# Main.net
KiCad netlist of a schematic drawn in Altium Designer
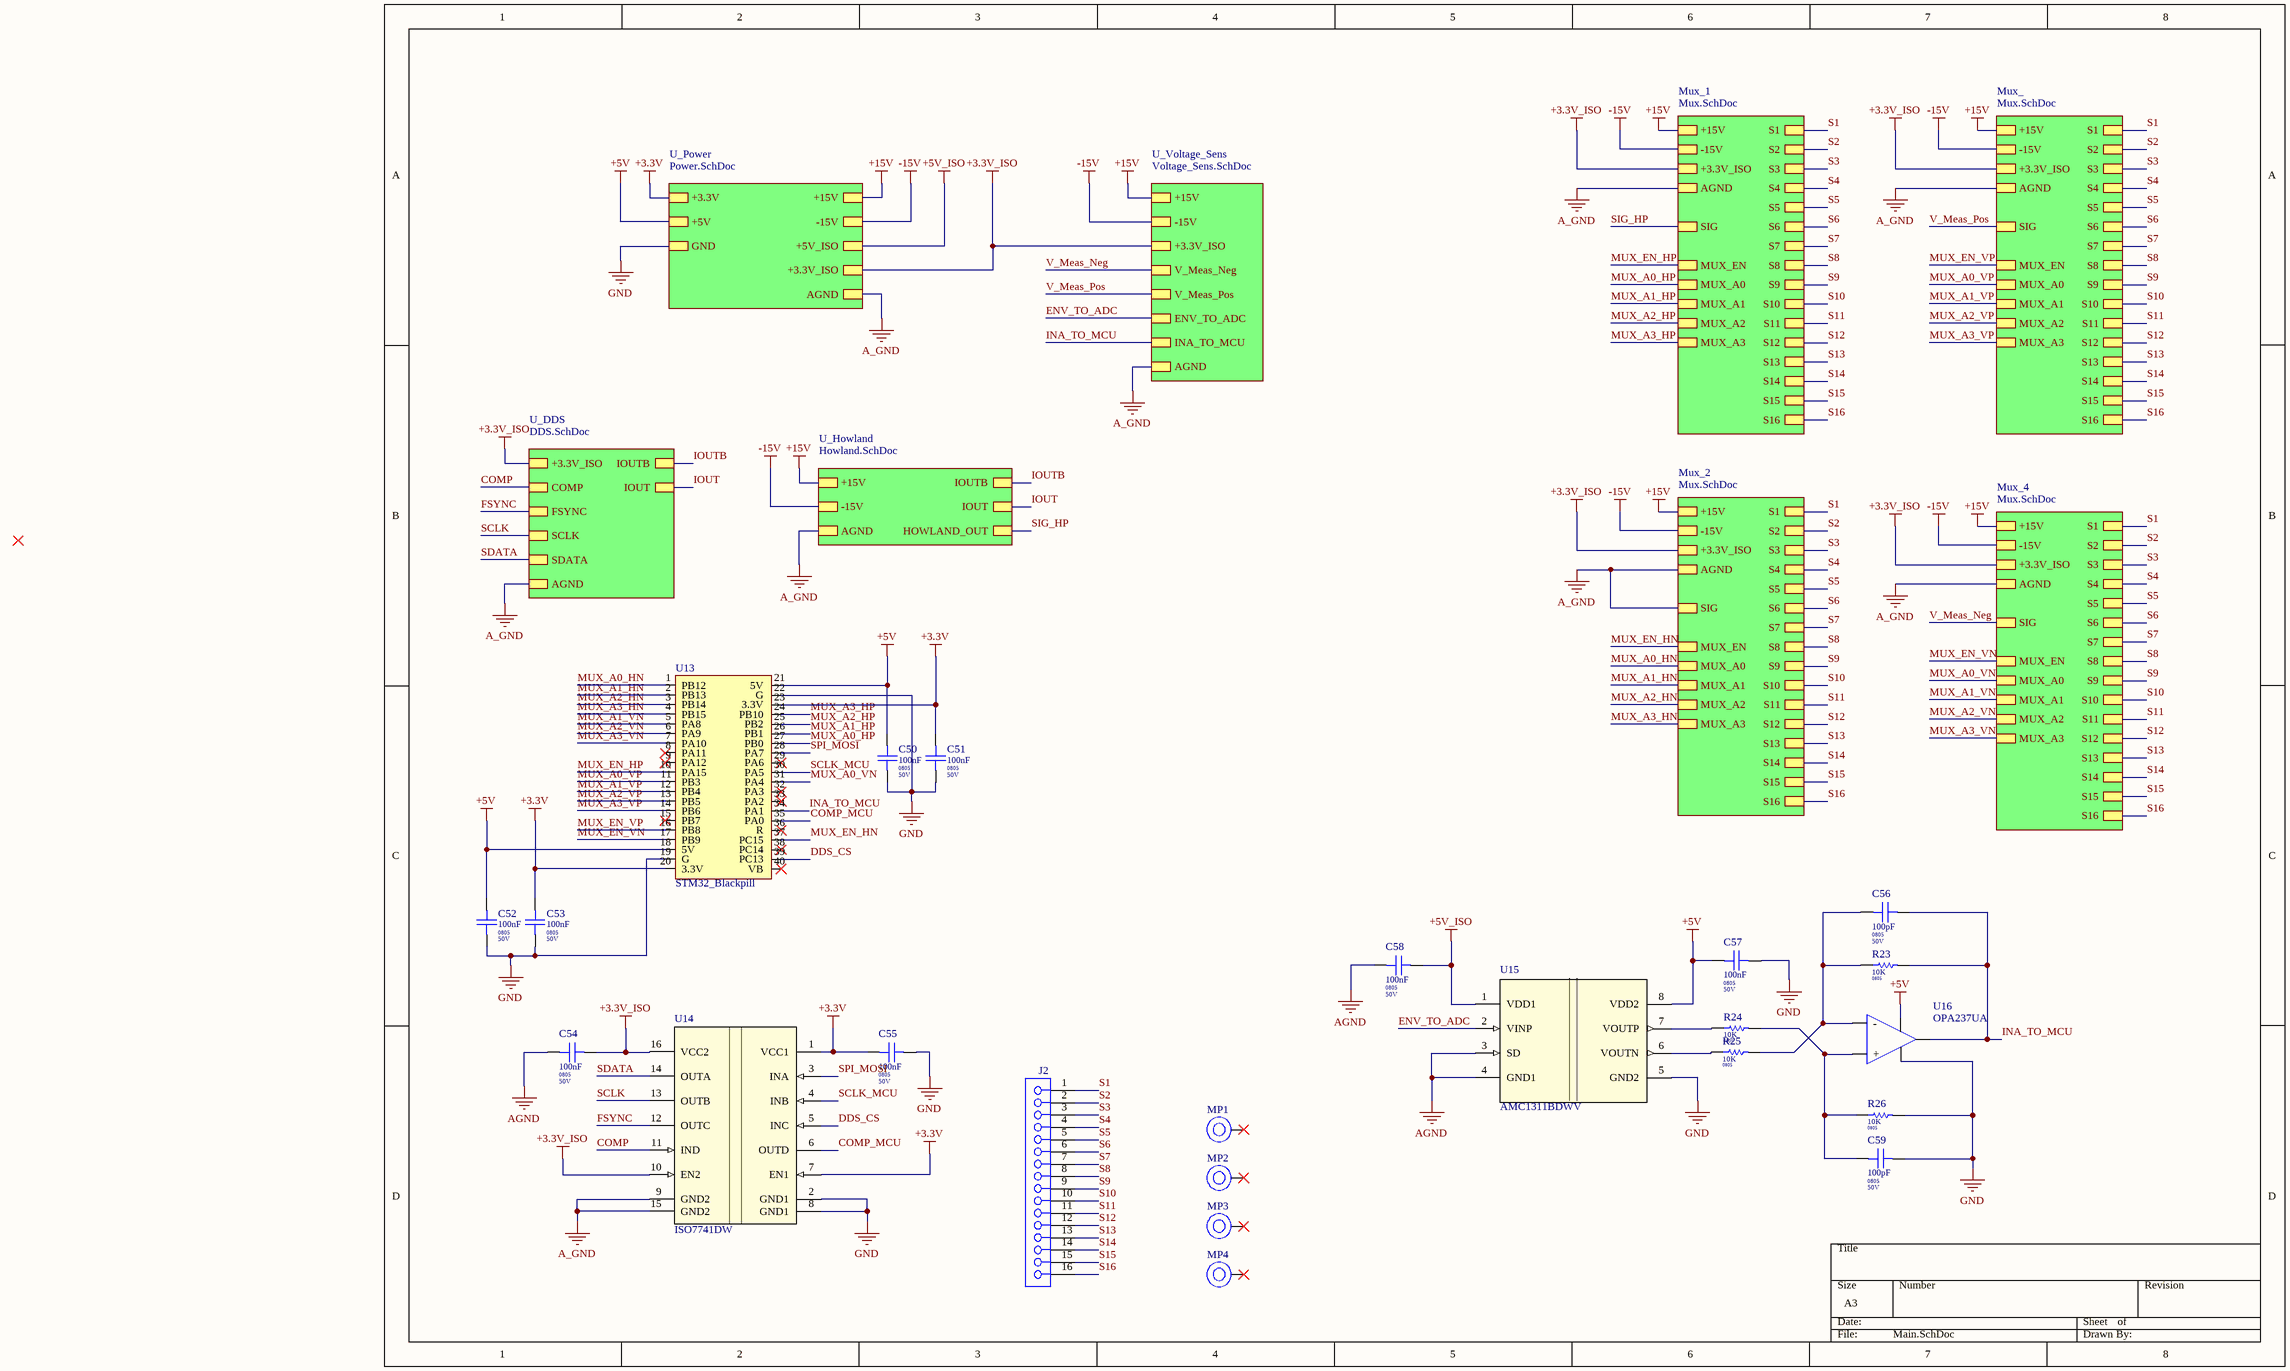
[diagram p0: Main.SchDoc]

(export (version "E")
  (design (tool "Eeschema 10.0.6"))
  (components
    (comp (ref "C50")
      (value "100nF")
      (footprint "CAPC 0805")
      (description "Capacitor Ceramic 100nF 50V 0805")
      (fields
        (field (name "TOLERANCE") "%10")
        (field (name "PACKAGE / CASE") "0805")
        (field (name "VOLTAGE") "50V")
        (field (name "PART NUMBER") "CAPC0572")
      )
      (libsource (lib "Aesk Database Library") (part "NPCapacitor"))
    )
    (comp (ref "C51")
      (value "100nF")
      (footprint "CAPC 0805")
      (description "Capacitor Ceramic 100nF 50V 0805")
      (fields
        (field (name "TOLERANCE") "%10")
        (field (name "PACKAGE / CASE") "0805")
        (field (name "VOLTAGE") "50V")
        (field (name "PART NUMBER") "CAPC0572")
      )
      (libsource (lib "Aesk Database Library") (part "NPCapacitor"))
    )
    (comp (ref "C52")
      (value "100nF")
      (footprint "CAPC 0805")
      (description "Capacitor Ceramic 100nF 50V 0805")
      (fields
        (field (name "TOLERANCE") "%10")
        (field (name "PACKAGE / CASE") "0805")
        (field (name "VOLTAGE") "50V")
        (field (name "PART NUMBER") "CAPC0572")
      )
      (libsource (lib "Aesk Database Library") (part "NPCapacitor"))
    )
    (comp (ref "C53")
      (value "100nF")
      (footprint "CAPC 0805")
      (description "Capacitor Ceramic 100nF 50V 0805")
      (fields
        (field (name "TOLERANCE") "%10")
        (field (name "PACKAGE / CASE") "0805")
        (field (name "VOLTAGE") "50V")
        (field (name "PART NUMBER") "CAPC0572")
      )
      (libsource (lib "Aesk Database Library") (part "NPCapacitor"))
    )
    (comp (ref "C54")
      (value "100nF")
      (footprint "CAPC 0805")
      (description "Capacitor Ceramic 100nF 50V 0805")
      (fields
        (field (name "TOLERANCE") "%10")
        (field (name "PACKAGE / CASE") "0805")
        (field (name "VOLTAGE") "50V")
        (field (name "PART NUMBER") "CAPC0572")
      )
      (libsource (lib "Aesk Database Library") (part "NPCapacitor"))
    )
    (comp (ref "C55")
      (value "100nF")
      (footprint "CAPC 0805")
      (description "Capacitor Ceramic 100nF 50V 0805")
      (fields
        (field (name "TOLERANCE") "%10")
        (field (name "PACKAGE / CASE") "0805")
        (field (name "VOLTAGE") "50V")
        (field (name "PART NUMBER") "CAPC0572")
      )
      (libsource (lib "Aesk Database Library") (part "NPCapacitor"))
    )
    (comp (ref "C56")
      (value "100pF")
      (footprint "CAPC 0805")
      (description "Capacitor Ceramic 100pF 50V 0805")
      (fields
        (field (name "TOLERANCE") "%10")
        (field (name "PACKAGE / CASE") "0805")
        (field (name "VOLTAGE") "50V")
        (field (name "PART NUMBER") "CAPC0548")
      )
      (libsource (lib "Aesk Database Library") (part "NPCapacitor"))
    )
    (comp (ref "C57")
      (value "100nF")
      (footprint "CAPC 0805")
      (description "Capacitor Ceramic 100nF 50V 0805")
      (fields
        (field (name "TOLERANCE") "%10")
        (field (name "PACKAGE / CASE") "0805")
        (field (name "VOLTAGE") "50V")
        (field (name "PART NUMBER") "CAPC0572")
      )
      (libsource (lib "Aesk Database Library") (part "NPCapacitor"))
    )
    (comp (ref "C58")
      (value "100nF")
      (footprint "CAPC 0805")
      (description "Capacitor Ceramic 100nF 50V 0805")
      (fields
        (field (name "TOLERANCE") "%10")
        (field (name "PACKAGE / CASE") "0805")
        (field (name "VOLTAGE") "50V")
        (field (name "PART NUMBER") "CAPC0572")
      )
      (libsource (lib "Aesk Database Library") (part "NPCapacitor"))
    )
    (comp (ref "C59")
      (value "100pF")
      (footprint "CAPC 0805")
      (description "Capacitor Ceramic 100pF 50V 0805")
      (fields
        (field (name "TOLERANCE") "%10")
        (field (name "PACKAGE / CASE") "0805")
        (field (name "VOLTAGE") "50V")
        (field (name "PART NUMBER") "CAPC0548")
      )
      (libsource (lib "Aesk Database Library") (part "NPCapacitor"))
    )
    (comp (ref "J2")
      (value "61301611821")
      (footprint "61301611821")
      (description "WR-PHD Socket Header, THT, Vertical, pitch 2.54mm, 1 Row, 16P")
      (fields (field (name "MANUFACTURER") "Wurth Elektronik"))
      (libsource (lib "WE - Electromechanical Components") (part "Header_Female_1R_16P"))
    )
    (comp (ref "MP1")
      (value "M3 x 15mm")
      (footprint "78614150360")
      (description "WA-SMSA SMT Spacer Studs Automotive, OD 6mm, ID 4.2mm, M3 x 15mm")
      (fields
        (field (name "MANUFACTURER PART NUMBER") "78614150360")
        (field (name "MANUFACTURER") "Wurth Elektronik")
      )
      (libsource (lib "WE - Electromechanical Components") (part "Spacer"))
    )
    (comp (ref "MP2")
      (value "M3 x 15mm")
      (footprint "78614150360")
      (description "WA-SMSA SMT Spacer Studs Automotive, OD 6mm, ID 4.2mm, M3 x 15mm")
      (fields
        (field (name "MANUFACTURER PART NUMBER") "78614150360")
        (field (name "MANUFACTURER") "Wurth Elektronik")
      )
      (libsource (lib "WE - Electromechanical Components") (part "Spacer"))
    )
    (comp (ref "MP3")
      (value "M3 x 15mm")
      (footprint "78614150360")
      (description "WA-SMSA SMT Spacer Studs Automotive, OD 6mm, ID 4.2mm, M3 x 15mm")
      (fields
        (field (name "MANUFACTURER PART NUMBER") "78614150360")
        (field (name "MANUFACTURER") "Wurth Elektronik")
      )
      (libsource (lib "WE - Electromechanical Components") (part "Spacer"))
    )
    (comp (ref "MP4")
      (value "M3 x 15mm")
      (footprint "78614150360")
      (description "WA-SMSA SMT Spacer Studs Automotive, OD 6mm, ID 4.2mm, M3 x 15mm")
      (fields
        (field (name "MANUFACTURER PART NUMBER") "78614150360")
        (field (name "MANUFACTURER") "Wurth Elektronik")
      )
      (libsource (lib "WE - Electromechanical Components") (part "Spacer"))
    )
    (comp (ref "R23")
      (value "10K")
      (footprint "RESC 0805")
      (description "10K 0805")
      (fields
        (field (name "TOLERANCE") "%5")
        (field (name "POWER") "1/10W")
        (field (name "PACKAGE / CASE") "0805")
      )
      (libsource (lib "Aesk Database Library") (part "Resistor"))
    )
    (comp (ref "R24")
      (value "10K")
      (footprint "RESC 0805")
      (description "10K 0805")
      (fields
        (field (name "TOLERANCE") "%5")
        (field (name "POWER") "1/10W")
        (field (name "PACKAGE / CASE") "0805")
      )
      (libsource (lib "Aesk Database Library") (part "Resistor"))
    )
    (comp (ref "R25")
      (value "10K")
      (footprint "RESC 0805")
      (description "10K 0805")
      (fields
        (field (name "TOLERANCE") "%5")
        (field (name "POWER") "1/10W")
        (field (name "PACKAGE / CASE") "0805")
      )
      (libsource (lib "Aesk Database Library") (part "Resistor"))
    )
    (comp (ref "R26")
      (value "10K")
      (footprint "RESC 0805")
      (description "10K 0805")
      (fields
        (field (name "TOLERANCE") "%5")
        (field (name "POWER") "1/10W")
        (field (name "PACKAGE / CASE") "0805")
      )
      (libsource (lib "Aesk Database Library") (part "Resistor"))
    )
    (comp (ref "U13")
      (value "STM32_Blackpill")
      (footprint "STM32_Blackpıll")
      (libsource (lib "Schlib1") (part "STM32_Blackpill"))
    )
    (comp (ref "U14")
      (value "ISO7741DW")
      (footprint "DW0016B_M")
      (description "Robust EMC, quad-channel, 3/1, reinforced digital isolator 16-SOIC -55 to 125")
      (fields (field (name "COPYRIGHT") "Copyright (C) 2026 Ultra Librarian. All rights reserved."))
      (libsource (lib "Schlib1") (part "ISO7741DW"))
    )
    (comp (ref "U15")
      (value "AMC1311BDWV")
      (footprint "DWV0008A")
      (description "2-V input, precision voltage sensing reinforced isolated amplifier 8-SOIC -55 to 125")
      (fields (field (name "COPYRIGHT") "Copyright (C) 2025 Ultra Librarian. All rights reserved."))
      (libsource (lib "Schlib1") (part "AMC1311BDWV"))
    )
    (comp (ref "U16")
      (value "OPA237UA")
      (footprint "SOIC127P599X175-8N")
      (description "Single-Supply Operational Amplifiers MicroAmplifier™ Series 8-SOIC -40 to 70")
      (fields (field (name "MANUFACTURER") "Texas Instruments"))
      (libsource (lib "Schlib1") (part "OPA237UA"))
    )
  )
  (nets
    (net (code "1") (name "+3.3V") (class "Default")
      (node (ref "C51") (pin "2") (pinfunction "2_2") (pintype "passive"))
      (node (ref "C53") (pin "2") (pinfunction "2_2") (pintype "passive"))
      (node (ref "C55") (pin "2") (pinfunction "2_2") (pintype "passive"))
      (node (ref "U13") (pin "20") (pinfunction "3.3V_20") (pintype "passive"))
      (node (ref "U13") (pin "23") (pinfunction "3.3V_23") (pintype "passive"))
      (node (ref "U14") (pin "1") (pinfunction "VCC1_1") (pintype "power_in"))
      (node (ref "U14") (pin "7") (pinfunction "EN1_7") (pintype "input"))
    )
    (net (code "2") (name "+3.3V_ISO") (class "Default")
      (node (ref "C54") (pin "1") (pinfunction "1_1") (pintype "passive"))
      (node (ref "U14") (pin "10") (pinfunction "EN2_10") (pintype "input"))
      (node (ref "U14") (pin "16") (pinfunction "VCC2_16") (pintype "power_in"))
    )
    (net (code "3") (name "+5V") (class "Default")
      (node (ref "C50") (pin "2") (pinfunction "2_2") (pintype "passive"))
      (node (ref "C52") (pin "2") (pinfunction "2_2") (pintype "passive"))
      (node (ref "C57") (pin "2") (pinfunction "2_2") (pintype "passive"))
      (node (ref "U13") (pin "18") (pinfunction "5V_18") (pintype "passive"))
      (node (ref "U13") (pin "21") (pinfunction "5V_21") (pintype "passive"))
      (node (ref "U15") (pin "8") (pinfunction "VDD2_8") (pintype "power_in"))
      (node (ref "U16") (pin "7") (pinfunction "V+_7") (pintype "passive"))
    )
    (net (code "4") (name "+5V_ISO") (class "Default")
      (node (ref "C58") (pin "1") (pinfunction "1_1") (pintype "passive"))
      (node (ref "U15") (pin "1") (pinfunction "VDD1_1") (pintype "power_in"))
    )
    (net (code "7") (name "/COMP") (class "Default")
      (node (ref "U14") (pin "11") (pinfunction "IND_11") (pintype "input"))
    )
    (net (code "8") (name "/COMP_MCU") (class "Default")
      (node (ref "U13") (pin "35") (pinfunction "PA0_35") (pintype "passive"))
      (node (ref "U14") (pin "6") (pinfunction "OUTD_6") (pintype "tri_state"))
    )
    (net (code "9") (name "/DDS_CS") (class "Default")
      (node (ref "U13") (pin "39") (pinfunction "PC13_39") (pintype "passive"))
      (node (ref "U14") (pin "5") (pinfunction "INC_5") (pintype "input"))
    )
    (net (code "10") (name "/ENV_TO_ADC") (class "Default")
      (node (ref "U15") (pin "2") (pinfunction "VINP_2") (pintype "input"))
    )
    (net (code "11") (name "/FSYNC") (class "Default")
      (node (ref "U14") (pin "12") (pinfunction "OUTC_12") (pintype "tri_state"))
    )
    (net (code "12") (name "/INA_TO_MCU") (class "Default")
      (node (ref "C56") (pin "2") (pinfunction "2_2") (pintype "passive"))
      (node (ref "R23") (pin "1") (pinfunction "1_1") (pintype "passive"))
      (node (ref "U13") (pin "34") (pinfunction "PA1_34") (pintype "passive"))
      (node (ref "U16") (pin "6") (pinfunction "Vout_6") (pintype "passive"))
    )
    (net (code "15") (name "/MUX_A0_HN") (class "Default")
      (node (ref "U13") (pin "1") (pinfunction "PB12_1") (pintype "passive"))
    )
    (net (code "16") (name "/MUX_A0_HP") (class "Default")
      (node (ref "U13") (pin "27") (pinfunction "PB0_27") (pintype "passive"))
    )
    (net (code "17") (name "/MUX_A0_VN") (class "Default")
      (node (ref "U13") (pin "31") (pinfunction "PA4_31") (pintype "passive"))
    )
    (net (code "18") (name "/MUX_A0_VP") (class "Default")
      (node (ref "U13") (pin "11") (pinfunction "PB3_11") (pintype "passive"))
    )
    (net (code "19") (name "/MUX_A1_HN") (class "Default")
      (node (ref "U13") (pin "2") (pinfunction "PB13_2") (pintype "passive"))
    )
    (net (code "20") (name "/MUX_A1_HP") (class "Default")
      (node (ref "U13") (pin "26") (pinfunction "PB1_26") (pintype "passive"))
    )
    (net (code "21") (name "/MUX_A1_VN") (class "Default")
      (node (ref "U13") (pin "5") (pinfunction "PA8_5") (pintype "passive"))
    )
    (net (code "22") (name "/MUX_A1_VP") (class "Default")
      (node (ref "U13") (pin "12") (pinfunction "PB4_12") (pintype "passive"))
    )
    (net (code "23") (name "/MUX_A2_HN") (class "Default")
      (node (ref "U13") (pin "3") (pinfunction "PB14_3") (pintype "passive"))
    )
    (net (code "24") (name "/MUX_A2_HP") (class "Default")
      (node (ref "U13") (pin "25") (pinfunction "PB2_25") (pintype "passive"))
    )
    (net (code "25") (name "/MUX_A2_VN") (class "Default")
      (node (ref "U13") (pin "6") (pinfunction "PA9_6") (pintype "passive"))
    )
    (net (code "26") (name "/MUX_A2_VP") (class "Default")
      (node (ref "U13") (pin "13") (pinfunction "PB5_13") (pintype "passive"))
    )
    (net (code "27") (name "/MUX_A3_HN") (class "Default")
      (node (ref "U13") (pin "4") (pinfunction "PB15_4") (pintype "passive"))
    )
    (net (code "28") (name "/MUX_A3_HP") (class "Default")
      (node (ref "U13") (pin "24") (pinfunction "PB10_24") (pintype "passive"))
    )
    (net (code "29") (name "/MUX_A3_VN") (class "Default")
      (node (ref "U13") (pin "7") (pinfunction "PA10_7") (pintype "passive"))
    )
    (net (code "30") (name "/MUX_A3_VP") (class "Default")
      (node (ref "U13") (pin "14") (pinfunction "PB6_14") (pintype "passive"))
    )
    (net (code "31") (name "/MUX_EN_HN") (class "Default")
      (node (ref "U13") (pin "37") (pinfunction "PC15_37") (pintype "passive"))
    )
    (net (code "32") (name "/MUX_EN_HP") (class "Default")
      (node (ref "U13") (pin "10") (pinfunction "PA15_10") (pintype "passive"))
    )
    (net (code "33") (name "/MUX_EN_VN") (class "Default")
      (node (ref "U13") (pin "17") (pinfunction "PB9_17") (pintype "passive"))
    )
    (net (code "34") (name "/MUX_EN_VP") (class "Default")
      (node (ref "U13") (pin "16") (pinfunction "PB8_16") (pintype "passive"))
    )
    (net (code "35") (name "/S1") (class "Default")
      (node (ref "J2") (pin "1") (pinfunction "1_1") (pintype "passive"))
    )
    (net (code "36") (name "/S2") (class "Default")
      (node (ref "J2") (pin "2") (pinfunction "2_2") (pintype "passive"))
    )
    (net (code "37") (name "/S3") (class "Default")
      (node (ref "J2") (pin "3") (pinfunction "3_3") (pintype "passive"))
    )
    (net (code "38") (name "/S4") (class "Default")
      (node (ref "J2") (pin "4") (pinfunction "4_4") (pintype "passive"))
    )
    (net (code "39") (name "/S5") (class "Default")
      (node (ref "J2") (pin "5") (pinfunction "5_5") (pintype "passive"))
    )
    (net (code "40") (name "/S6") (class "Default")
      (node (ref "J2") (pin "6") (pinfunction "6_6") (pintype "passive"))
    )
    (net (code "41") (name "/S7") (class "Default")
      (node (ref "J2") (pin "7") (pinfunction "7_7") (pintype "passive"))
    )
    (net (code "42") (name "/S8") (class "Default")
      (node (ref "J2") (pin "8") (pinfunction "8_8") (pintype "passive"))
    )
    (net (code "43") (name "/S9") (class "Default")
      (node (ref "J2") (pin "9") (pinfunction "9_9") (pintype "passive"))
    )
    (net (code "44") (name "/S10") (class "Default")
      (node (ref "J2") (pin "10") (pinfunction "10_10") (pintype "passive"))
    )
    (net (code "45") (name "/S11") (class "Default")
      (node (ref "J2") (pin "11") (pinfunction "11_11") (pintype "passive"))
    )
    (net (code "46") (name "/S12") (class "Default")
      (node (ref "J2") (pin "12") (pinfunction "12_12") (pintype "passive"))
    )
    (net (code "47") (name "/S13") (class "Default")
      (node (ref "J2") (pin "13") (pinfunction "13_13") (pintype "passive"))
    )
    (net (code "48") (name "/S14") (class "Default")
      (node (ref "J2") (pin "14") (pinfunction "14_14") (pintype "passive"))
    )
    (net (code "49") (name "/S15") (class "Default")
      (node (ref "J2") (pin "15") (pinfunction "15_15") (pintype "passive"))
    )
    (net (code "50") (name "/S16") (class "Default")
      (node (ref "J2") (pin "16") (pinfunction "16_16") (pintype "passive"))
    )
    (net (code "51") (name "/SCLK") (class "Default")
      (node (ref "U14") (pin "13") (pinfunction "OUTB_13") (pintype "tri_state"))
    )
    (net (code "52") (name "/SCLK_MCU") (class "Default")
      (node (ref "U13") (pin "30") (pinfunction "PA5_30") (pintype "passive"))
      (node (ref "U14") (pin "4") (pinfunction "INB_4") (pintype "input"))
    )
    (net (code "53") (name "/SDATA") (class "Default")
      (node (ref "U14") (pin "14") (pinfunction "OUTA_14") (pintype "tri_state"))
    )
    (net (code "55") (name "/SPI_MOSI") (class "Default")
      (node (ref "U13") (pin "28") (pinfunction "PA7_28") (pintype "passive"))
      (node (ref "U14") (pin "3") (pinfunction "INA_3") (pintype "input"))
    )
    (net (code "58") (name "AGND") (class "Default")
      (node (ref "C54") (pin "2") (pinfunction "2_2") (pintype "passive"))
      (node (ref "C58") (pin "2") (pinfunction "2_2") (pintype "passive"))
      (node (ref "U15") (pin "3") (pinfunction "SD_3") (pintype "input"))
      (node (ref "U15") (pin "4") (pinfunction "GND1_4") (pintype "power_in"))
    )
    (net (code "59") (name "A_GND") (class "Default")
      (node (ref "U14") (pin "15") (pinfunction "GND2_15") (pintype "power_in"))
      (node (ref "U14") (pin "9") (pinfunction "GND2_9") (pintype "power_in"))
    )
    (net (code "60") (name "GND") (class "Default")
      (node (ref "C50") (pin "1") (pinfunction "1_1") (pintype "passive"))
      (node (ref "C51") (pin "1") (pinfunction "1_1") (pintype "passive"))
      (node (ref "C52") (pin "1") (pinfunction "1_1") (pintype "passive"))
      (node (ref "C53") (pin "1") (pinfunction "1_1") (pintype "passive"))
      (node (ref "C55") (pin "1") (pinfunction "1_1") (pintype "passive"))
      (node (ref "C57") (pin "1") (pinfunction "1_1") (pintype "passive"))
      (node (ref "C59") (pin "2") (pinfunction "2_2") (pintype "passive"))
      (node (ref "R26") (pin "1") (pinfunction "1_1") (pintype "passive"))
      (node (ref "U13") (pin "19") (pinfunction "G_19") (pintype "passive"))
      (node (ref "U13") (pin "22") (pinfunction "G_22") (pintype "passive"))
      (node (ref "U14") (pin "2") (pinfunction "GND1_2") (pintype "power_in"))
      (node (ref "U14") (pin "8") (pinfunction "GND1_8") (pintype "power_in"))
      (node (ref "U15") (pin "5") (pinfunction "GND2_5") (pintype "power_in"))
      (node (ref "U16") (pin "4") (pinfunction "V-_4") (pintype "passive"))
    )
    (net (code "61") (name "Net-(U15-VOUTN)") (class "Default")
      (node (ref "R25") (pin "2") (pinfunction "2_2") (pintype "passive"))
      (node (ref "U15") (pin "6") (pinfunction "VOUTN_6") (pintype "output"))
    )
    (net (code "62") (name "Net-(U15-VOUTP)") (class "Default")
      (node (ref "R24") (pin "2") (pinfunction "2_2") (pintype "passive"))
      (node (ref "U15") (pin "7") (pinfunction "VOUTP_7") (pintype "output"))
    )
    (net (code "63") (name "Net-(U16-+)") (class "Default")
      (node (ref "C59") (pin "1") (pinfunction "1_1") (pintype "passive"))
      (node (ref "R24") (pin "1") (pinfunction "1_1") (pintype "passive"))
      (node (ref "R26") (pin "2") (pinfunction "2_2") (pintype "passive"))
      (node (ref "U16") (pin "3") (pinfunction "+_3") (pintype "passive"))
    )
    (net (code "64") (name "Net-(U16--)") (class "Default")
      (node (ref "C56") (pin "1") (pinfunction "1_1") (pintype "passive"))
      (node (ref "R23") (pin "2") (pinfunction "2_2") (pintype "passive"))
      (node (ref "R25") (pin "1") (pinfunction "1_1") (pintype "passive"))
      (node (ref "U16") (pin "2") (pinfunction "-_2") (pintype "passive"))
    )
    (net (code "65") (name "unconnected-(MP1-Pad1)") (class "Default")
      (node (ref "MP1") (pin "1") (pinfunction "1_1") (pintype "passive+no_connect"))
    )
    (net (code "66") (name "unconnected-(MP2-Pad1)") (class "Default")
      (node (ref "MP2") (pin "1") (pinfunction "1_1") (pintype "passive+no_connect"))
    )
    (net (code "67") (name "unconnected-(MP3-Pad1)") (class "Default")
      (node (ref "MP3") (pin "1") (pinfunction "1_1") (pintype "passive+no_connect"))
    )
    (net (code "68") (name "unconnected-(MP4-Pad1)") (class "Default")
      (node (ref "MP4") (pin "1") (pinfunction "1_1") (pintype "passive+no_connect"))
    )
    (net (code "69") (name "unconnected-(U13-PA2-Pad33)") (class "Default")
      (node (ref "U13") (pin "33") (pinfunction "PA2_33") (pintype "passive+no_connect"))
    )
    (net (code "70") (name "unconnected-(U13-PA3-Pad32)") (class "Default")
      (node (ref "U13") (pin "32") (pinfunction "PA3_32") (pintype "passive+no_connect"))
    )
    (net (code "71") (name "unconnected-(U13-PA6-Pad29)") (class "Default")
      (node (ref "U13") (pin "29") (pinfunction "PA6_29") (pintype "passive+no_connect"))
    )
    (net (code "72") (name "unconnected-(U13-PA11-Pad8)") (class "Default")
      (node (ref "U13") (pin "8") (pinfunction "PA11_8") (pintype "passive+no_connect"))
    )
    (net (code "73") (name "unconnected-(U13-PA12-Pad9)") (class "Default")
      (node (ref "U13") (pin "9") (pinfunction "PA12_9") (pintype "passive+no_connect"))
    )
    (net (code "74") (name "unconnected-(U13-PB7-Pad15)") (class "Default")
      (node (ref "U13") (pin "15") (pinfunction "PB7_15") (pintype "passive+no_connect"))
    )
    (net (code "75") (name "unconnected-(U13-PC14-Pad38)") (class "Default")
      (node (ref "U13") (pin "38") (pinfunction "PC14_38") (pintype "passive+no_connect"))
    )
    (net (code "76") (name "unconnected-(U13-R-Pad36)") (class "Default")
      (node (ref "U13") (pin "36") (pinfunction "R_36") (pintype "passive+no_connect"))
    )
    (net (code "77") (name "unconnected-(U13-VB-Pad40)") (class "Default")
      (node (ref "U13") (pin "40") (pinfunction "VB_40") (pintype "passive+no_connect"))
    )
  )
)
